# ADC_LED.net
KiCad netlist of a schematic drawn in EAGLE
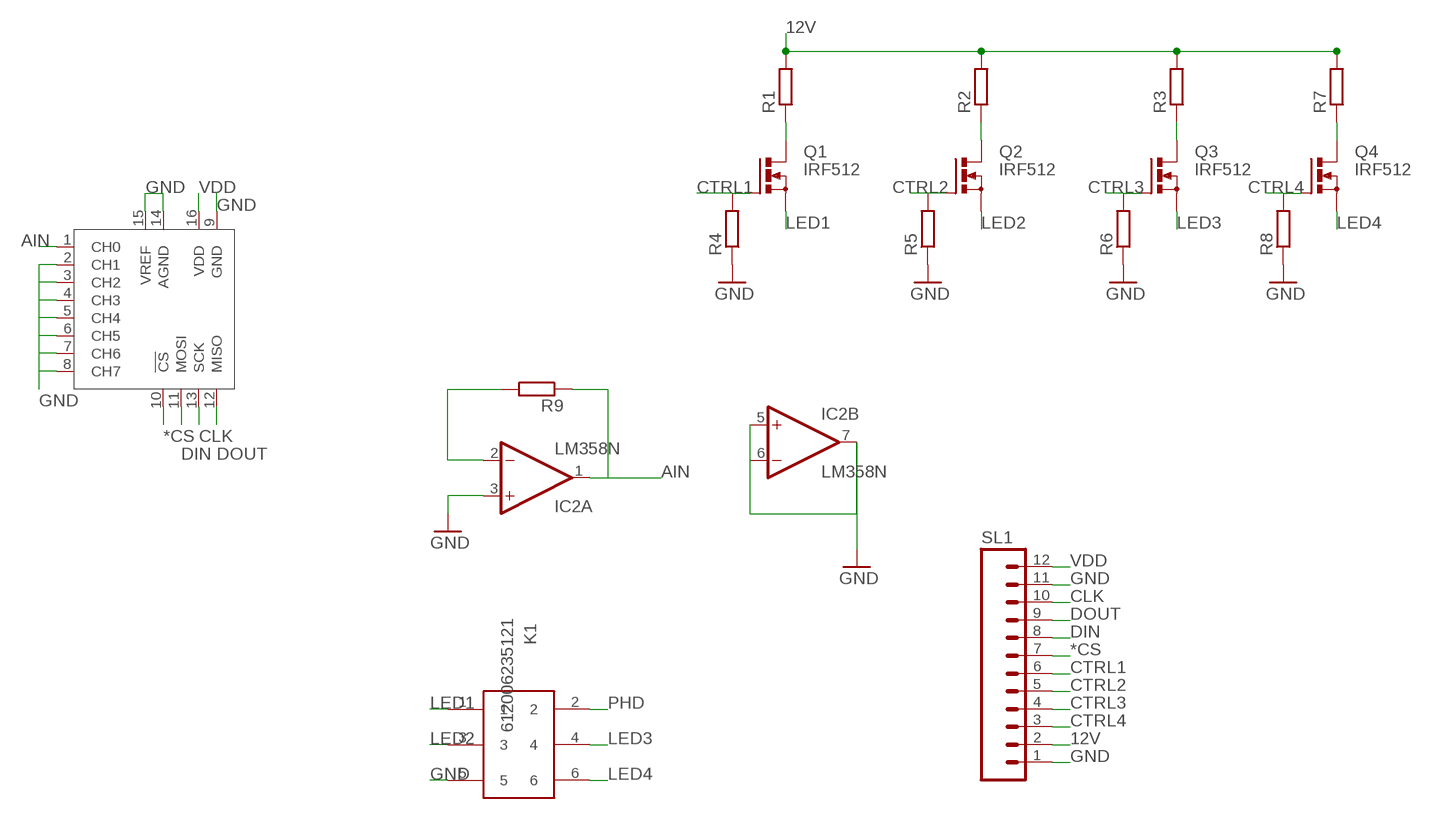
[diagram p0: schematic, sheet 1]

(export (version "E")
  (design (tool "Eeschema 10.0.6"))
  (components
    (comp (ref "IC2")
      (value "LM358N")
      (footprint "eagle-import:DIL08")
      (libsource (lib "eagle-import") (part "LM358N"))
    )
    (comp (ref "K1")
      (value "612006235121")
      (footprint "eagle-import:612006235121")
      (libsource (lib "eagle-import") (part "612006235121"))
    )
    (comp (ref "Q1")
      (value "IRF512")
      (footprint "eagle-import:TO220BV")
      (libsource (lib "eagle-import") (part "IRF512"))
    )
    (comp (ref "Q2")
      (value "IRF512")
      (footprint "eagle-import:TO220BV")
      (libsource (lib "eagle-import") (part "IRF512"))
    )
    (comp (ref "Q3")
      (value "IRF512")
      (footprint "eagle-import:TO220BV")
      (libsource (lib "eagle-import") (part "IRF512"))
    )
    (comp (ref "Q4")
      (value "IRF512")
      (footprint "eagle-import:TO220BV")
      (libsource (lib "eagle-import") (part "IRF512"))
    )
    (comp (ref "R1")
      (value "R-EU_0204/7")
      (footprint "eagle-import:0204_7")
      (libsource (lib "eagle-import") (part "R-EU_0204/7"))
    )
    (comp (ref "R2")
      (value "R-EU_0204/7")
      (footprint "eagle-import:0204_7")
      (libsource (lib "eagle-import") (part "R-EU_0204/7"))
    )
    (comp (ref "R3")
      (value "R-EU_0204/7")
      (footprint "eagle-import:0204_7")
      (libsource (lib "eagle-import") (part "R-EU_0204/7"))
    )
    (comp (ref "R4")
      (value "R-EU_0204/7")
      (footprint "eagle-import:0204_7")
      (libsource (lib "eagle-import") (part "R-EU_0204/7"))
    )
    (comp (ref "R5")
      (value "R-EU_0204/7")
      (footprint "eagle-import:0204_7")
      (libsource (lib "eagle-import") (part "R-EU_0204/7"))
    )
    (comp (ref "R6")
      (value "R-EU_0204/7")
      (footprint "eagle-import:0204_7")
      (libsource (lib "eagle-import") (part "R-EU_0204/7"))
    )
    (comp (ref "R7")
      (value "R-EU_0204/7")
      (footprint "eagle-import:0204_7")
      (libsource (lib "eagle-import") (part "R-EU_0204/7"))
    )
    (comp (ref "R8")
      (value "R-EU_0204/7")
      (footprint "eagle-import:0204_7")
      (libsource (lib "eagle-import") (part "R-EU_0204/7"))
    )
    (comp (ref "R9")
      (value "R-EU_0204/7")
      (footprint "eagle-import:0204_7")
      (libsource (lib "eagle-import") (part "R-EU_0204/7"))
    )
    (comp (ref "SL1")
      (value "M12")
      (footprint "eagle-import:12P")
      (libsource (lib "eagle-import") (part "M12"))
    )
    (comp (ref "U$2")
      (value "MCP3008P")
      (footprint "eagle-import:DIL16")
      (libsource (lib "eagle-import") (part "MCP3008P"))
    )
  )
  (nets
    (net (code "1") (name "/*CS") (class "Default")
      (node (ref "SL1") (pin "7") (pinfunction "7_7") (pintype "passive"))
      (node (ref "U$2") (pin "10") (pinfunction "~{CS}_10") (pintype "input"))
    )
    (net (code "2") (name "/12V") (class "Default")
      (node (ref "R1") (pin "2") (pinfunction "2_2") (pintype "passive"))
      (node (ref "R2") (pin "2") (pinfunction "2_2") (pintype "passive"))
      (node (ref "R3") (pin "2") (pinfunction "2_2") (pintype "passive"))
      (node (ref "R7") (pin "2") (pinfunction "2_2") (pintype "passive"))
      (node (ref "SL1") (pin "2") (pinfunction "2_2") (pintype "passive"))
    )
    (net (code "3") (name "/AIN") (class "Default")
      (node (ref "IC2") (pin "1") (pinfunction "OUT_1") (pintype "output"))
      (node (ref "R9") (pin "1") (pinfunction "1_1") (pintype "passive"))
      (node (ref "U$2") (pin "1") (pinfunction "CH0_1") (pintype "input"))
    )
    (net (code "4") (name "/CLK") (class "Default")
      (node (ref "SL1") (pin "10") (pinfunction "10_10") (pintype "passive"))
      (node (ref "U$2") (pin "13") (pinfunction "SCK_13") (pintype "input"))
    )
    (net (code "5") (name "/CTRL1") (class "Default")
      (node (ref "Q1") (pin "G") (pinfunction "G_G") (pintype "passive"))
      (node (ref "R4") (pin "2") (pinfunction "2_2") (pintype "passive"))
      (node (ref "SL1") (pin "6") (pinfunction "6_6") (pintype "passive"))
    )
    (net (code "6") (name "/CTRL2") (class "Default")
      (node (ref "Q2") (pin "G") (pinfunction "G_G") (pintype "passive"))
      (node (ref "R5") (pin "2") (pinfunction "2_2") (pintype "passive"))
      (node (ref "SL1") (pin "5") (pinfunction "5_5") (pintype "passive"))
    )
    (net (code "7") (name "/CTRL3") (class "Default")
      (node (ref "Q3") (pin "G") (pinfunction "G_G") (pintype "passive"))
      (node (ref "R6") (pin "2") (pinfunction "2_2") (pintype "passive"))
      (node (ref "SL1") (pin "4") (pinfunction "4_4") (pintype "passive"))
    )
    (net (code "8") (name "/CTRL4") (class "Default")
      (node (ref "Q4") (pin "G") (pinfunction "G_G") (pintype "passive"))
      (node (ref "R8") (pin "2") (pinfunction "2_2") (pintype "passive"))
      (node (ref "SL1") (pin "3") (pinfunction "3_3") (pintype "passive"))
    )
    (net (code "9") (name "/DIN") (class "Default")
      (node (ref "SL1") (pin "8") (pinfunction "8_8") (pintype "passive"))
      (node (ref "U$2") (pin "11") (pinfunction "MOSI_11") (pintype "input"))
    )
    (net (code "10") (name "/DOUT") (class "Default")
      (node (ref "SL1") (pin "9") (pinfunction "9_9") (pintype "passive"))
      (node (ref "U$2") (pin "12") (pinfunction "MISO_12") (pintype "output"))
    )
    (net (code "11") (name "/LED1") (class "Default")
      (node (ref "K1") (pin "1") (pinfunction "1_1") (pintype "passive"))
      (node (ref "Q1") (pin "S") (pinfunction "S_S") (pintype "passive"))
    )
    (net (code "12") (name "/LED2") (class "Default")
      (node (ref "K1") (pin "3") (pinfunction "3_3") (pintype "passive"))
      (node (ref "Q2") (pin "S") (pinfunction "S_S") (pintype "passive"))
    )
    (net (code "13") (name "/LED3") (class "Default")
      (node (ref "K1") (pin "4") (pinfunction "4_4") (pintype "passive"))
      (node (ref "Q3") (pin "S") (pinfunction "S_S") (pintype "passive"))
    )
    (net (code "14") (name "/LED4") (class "Default")
      (node (ref "K1") (pin "6") (pinfunction "6_6") (pintype "passive"))
      (node (ref "Q4") (pin "S") (pinfunction "S_S") (pintype "passive"))
    )
    (net (code "15") (name "/PHD") (class "Default")
      (node (ref "IC2") (pin "2") (pinfunction "-IN_2") (pintype "input"))
      (node (ref "K1") (pin "2") (pinfunction "2_2") (pintype "passive"))
      (node (ref "R9") (pin "2") (pinfunction "2_2") (pintype "passive"))
    )
    (net (code "16") (name "/VDD") (class "Default")
      (node (ref "SL1") (pin "12") (pinfunction "12_12") (pintype "passive"))
      (node (ref "U$2") (pin "16") (pinfunction "VDD_16") (pintype "power_in"))
    )
    (net (code "17") (name "GND") (class "Default")
      (node (ref "IC2") (pin "3") (pinfunction "+IN_3") (pintype "input"))
      (node (ref "IC2") (pin "5") (pinfunction "+IN_5") (pintype "input"))
      (node (ref "IC2") (pin "6") (pinfunction "-IN_6") (pintype "input"))
      (node (ref "IC2") (pin "7") (pinfunction "OUT_7") (pintype "output"))
      (node (ref "K1") (pin "5") (pinfunction "5_5") (pintype "passive"))
      (node (ref "R4") (pin "1") (pinfunction "1_1") (pintype "passive"))
      (node (ref "R5") (pin "1") (pinfunction "1_1") (pintype "passive"))
      (node (ref "R6") (pin "1") (pinfunction "1_1") (pintype "passive"))
      (node (ref "R8") (pin "1") (pinfunction "1_1") (pintype "passive"))
      (node (ref "SL1") (pin "1") (pinfunction "1_1") (pintype "passive"))
      (node (ref "SL1") (pin "11") (pinfunction "11_11") (pintype "passive"))
      (node (ref "U$2") (pin "14") (pinfunction "AGND_14") (pintype "power_in"))
      (node (ref "U$2") (pin "15") (pinfunction "VREF_15") (pintype "power_in"))
      (node (ref "U$2") (pin "2") (pinfunction "CH1_2") (pintype "input"))
      (node (ref "U$2") (pin "3") (pinfunction "CH2_3") (pintype "input"))
      (node (ref "U$2") (pin "4") (pinfunction "CH3_4") (pintype "input"))
      (node (ref "U$2") (pin "5") (pinfunction "CH4_5") (pintype "input"))
      (node (ref "U$2") (pin "6") (pinfunction "CH5_6") (pintype "input"))
      (node (ref "U$2") (pin "7") (pinfunction "CH6_7") (pintype "input"))
      (node (ref "U$2") (pin "8") (pinfunction "CH7_8") (pintype "input"))
      (node (ref "U$2") (pin "9") (pinfunction "GND_9") (pintype "power_in"))
    )
    (net (code "18") (name "Net-(Q1-PadD)") (class "Default")
      (node (ref "Q1") (pin "D") (pinfunction "D_D") (pintype "passive"))
      (node (ref "R1") (pin "1") (pinfunction "1_1") (pintype "passive"))
    )
    (net (code "19") (name "Net-(Q2-PadD)") (class "Default")
      (node (ref "Q2") (pin "D") (pinfunction "D_D") (pintype "passive"))
      (node (ref "R2") (pin "1") (pinfunction "1_1") (pintype "passive"))
    )
    (net (code "20") (name "Net-(Q3-PadD)") (class "Default")
      (node (ref "Q3") (pin "D") (pinfunction "D_D") (pintype "passive"))
      (node (ref "R3") (pin "1") (pinfunction "1_1") (pintype "passive"))
    )
    (net (code "21") (name "Net-(Q4-PadD)") (class "Default")
      (node (ref "Q4") (pin "D") (pinfunction "D_D") (pintype "passive"))
      (node (ref "R7") (pin "1") (pinfunction "1_1") (pintype "passive"))
    )
  )
)
